# digit_5.net
KiCad netlist of a schematic drawn in EAGLE
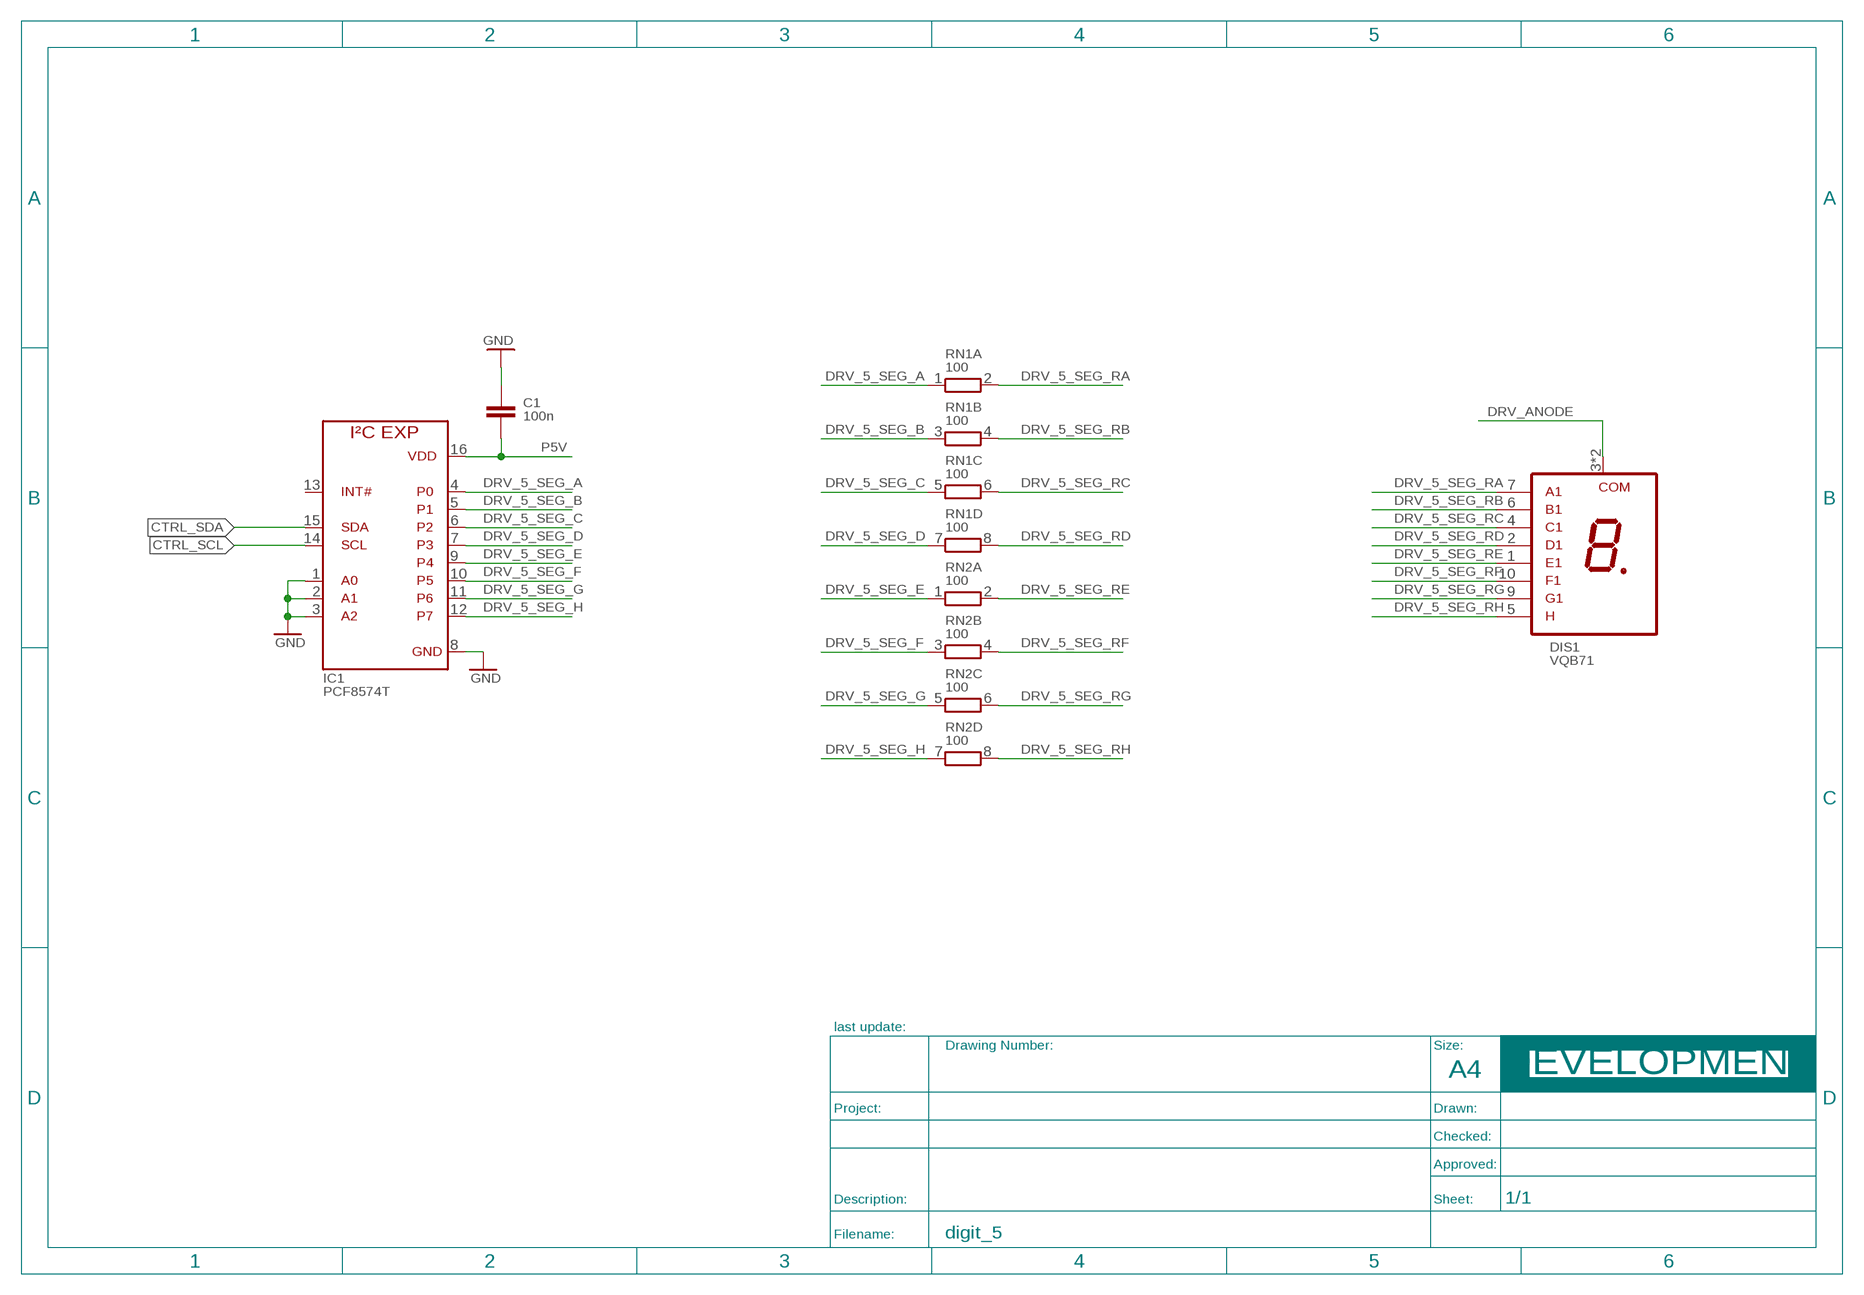
[diagram p0: schematic, sheet 1]

(export (version "E")
  (design (tool "Eeschema 10.0.6"))
  (components
    (comp (ref "C1")
      (value "100n")
      (footprint "eagle-import:S_0805")
      (fields (field (name "PART_CODE_BEL") "C_PAC_S_0805_VAL_100n"))
      (libsource (lib "eagle-import") (part "C_EU_S_0805"))
    )
    (comp (ref "DIS1")
      (value "VQB71")
      (footprint "eagle-import:T_VQB71")
      (libsource (lib "eagle-import") (part "VQB71"))
    )
    (comp (ref "IC1")
      (value "PCF8574T")
      (footprint "eagle-import:S_SOIC16")
      (libsource (lib "eagle-import") (part "PCF8574T"))
    )
    (comp (ref "RN1")
      (value "100")
      (footprint "eagle-import:T_SIL8")
      (fields (field (name "PART_CODE_BEL") "RN_PAC_T_SIL8_VAL_100"))
      (libsource (lib "eagle-import") (part "R_EU_ARRAY_4"))
    )
    (comp (ref "RN2")
      (value "100")
      (footprint "eagle-import:T_SIL8")
      (fields (field (name "PART_CODE_BEL") "RN_PAC_T_SIL8_VAL_100"))
      (libsource (lib "eagle-import") (part "R_EU_ARRAY_4"))
    )
  )
  (nets
    (net (code "1") (name "/DRV_5_SEG_A") (class "Default")
      (node (ref "IC1") (pin "4") (pinfunction "P0_4") (pintype "bidirectional"))
      (node (ref "RN1") (pin "1") (pinfunction "1_1") (pintype "passive"))
    )
    (net (code "2") (name "/DRV_5_SEG_B") (class "Default")
      (node (ref "IC1") (pin "5") (pinfunction "P1_5") (pintype "bidirectional"))
      (node (ref "RN1") (pin "3") (pinfunction "1_3") (pintype "passive"))
    )
    (net (code "3") (name "/DRV_5_SEG_C") (class "Default")
      (node (ref "IC1") (pin "6") (pinfunction "P2_6") (pintype "bidirectional"))
      (node (ref "RN1") (pin "5") (pinfunction "1_5") (pintype "passive"))
    )
    (net (code "4") (name "/DRV_5_SEG_D") (class "Default")
      (node (ref "IC1") (pin "7") (pinfunction "P3_7") (pintype "bidirectional"))
      (node (ref "RN1") (pin "7") (pinfunction "1_7") (pintype "passive"))
    )
    (net (code "5") (name "/DRV_5_SEG_E") (class "Default")
      (node (ref "IC1") (pin "9") (pinfunction "P4_9") (pintype "bidirectional"))
      (node (ref "RN2") (pin "1") (pinfunction "1_1") (pintype "passive"))
    )
    (net (code "6") (name "/DRV_5_SEG_F") (class "Default")
      (node (ref "IC1") (pin "10") (pinfunction "P5_10") (pintype "bidirectional"))
      (node (ref "RN2") (pin "3") (pinfunction "1_3") (pintype "passive"))
    )
    (net (code "7") (name "/DRV_5_SEG_G") (class "Default")
      (node (ref "IC1") (pin "11") (pinfunction "P6_11") (pintype "bidirectional"))
      (node (ref "RN2") (pin "5") (pinfunction "1_5") (pintype "passive"))
    )
    (net (code "8") (name "/DRV_5_SEG_H") (class "Default")
      (node (ref "IC1") (pin "12") (pinfunction "P7_12") (pintype "bidirectional"))
      (node (ref "RN2") (pin "7") (pinfunction "1_7") (pintype "passive"))
    )
    (net (code "9") (name "/DRV_5_SEG_RA") (class "Default")
      (node (ref "DIS1") (pin "7") (pinfunction "A1_7") (pintype "passive"))
      (node (ref "RN1") (pin "2") (pinfunction "2_2") (pintype "passive"))
    )
    (net (code "10") (name "/DRV_5_SEG_RB") (class "Default")
      (node (ref "DIS1") (pin "6") (pinfunction "B1_6") (pintype "passive"))
      (node (ref "RN1") (pin "4") (pinfunction "2_4") (pintype "passive"))
    )
    (net (code "11") (name "/DRV_5_SEG_RC") (class "Default")
      (node (ref "DIS1") (pin "4") (pinfunction "C1_4") (pintype "passive"))
      (node (ref "RN1") (pin "6") (pinfunction "2_6") (pintype "passive"))
    )
    (net (code "12") (name "/DRV_5_SEG_RD") (class "Default")
      (node (ref "DIS1") (pin "2") (pinfunction "D1_2") (pintype "passive"))
      (node (ref "RN1") (pin "8") (pinfunction "2_8") (pintype "passive"))
    )
    (net (code "13") (name "/DRV_5_SEG_RE") (class "Default")
      (node (ref "DIS1") (pin "1") (pinfunction "E1_1") (pintype "passive"))
      (node (ref "RN2") (pin "2") (pinfunction "2_2") (pintype "passive"))
    )
    (net (code "14") (name "/DRV_5_SEG_RF") (class "Default")
      (node (ref "DIS1") (pin "10") (pinfunction "F1_10") (pintype "passive"))
      (node (ref "RN2") (pin "4") (pinfunction "2_4") (pintype "passive"))
    )
    (net (code "15") (name "/DRV_5_SEG_RG") (class "Default")
      (node (ref "DIS1") (pin "9") (pinfunction "G1_9") (pintype "passive"))
      (node (ref "RN2") (pin "6") (pinfunction "2_6") (pintype "passive"))
    )
    (net (code "16") (name "/DRV_5_SEG_RH") (class "Default")
      (node (ref "DIS1") (pin "5") (pinfunction "DP1_5") (pintype "passive"))
      (node (ref "RN2") (pin "8") (pinfunction "2_8") (pintype "passive"))
    )
    (net (code "17") (name "/DRV_ANODE") (class "Default")
      (node (ref "DIS1") (pin "3") (pinfunction "COM1_3") (pintype "passive"))
      (node (ref "DIS1") (pin "8") (pinfunction "COM1_8") (pintype "passive"))
    )
    (net (code "18") (name "/P5V") (class "Default")
      (node (ref "C1") (pin "2") (pinfunction "2_2") (pintype "passive"))
      (node (ref "IC1") (pin "16") (pinfunction "VDD_16") (pintype "power_in"))
    )
    (net (code "19") (name "CTRL_SCL") (class "Default")
      (node (ref "IC1") (pin "14") (pinfunction "SCL_14") (pintype "input"))
    )
    (net (code "20") (name "CTRL_SDA") (class "Default")
      (node (ref "IC1") (pin "15") (pinfunction "SDA_15") (pintype "bidirectional"))
    )
    (net (code "21") (name "GND") (class "Default")
      (node (ref "C1") (pin "1") (pinfunction "1_1") (pintype "passive"))
      (node (ref "IC1") (pin "1") (pinfunction "A0_1") (pintype "input"))
      (node (ref "IC1") (pin "2") (pinfunction "A1_2") (pintype "input"))
      (node (ref "IC1") (pin "3") (pinfunction "A2_3") (pintype "input"))
      (node (ref "IC1") (pin "8") (pinfunction "GND_8") (pintype "power_in"))
    )
    (net (code "22") (name "unconnected-(IC1-~{INT}-Pad13)") (class "Default")
      (node (ref "IC1") (pin "13") (pinfunction "~{INT}_13") (pintype "output"))
    )
  )
)
